# Sheet1.net
KiCad netlist of a schematic drawn in Altium Designer
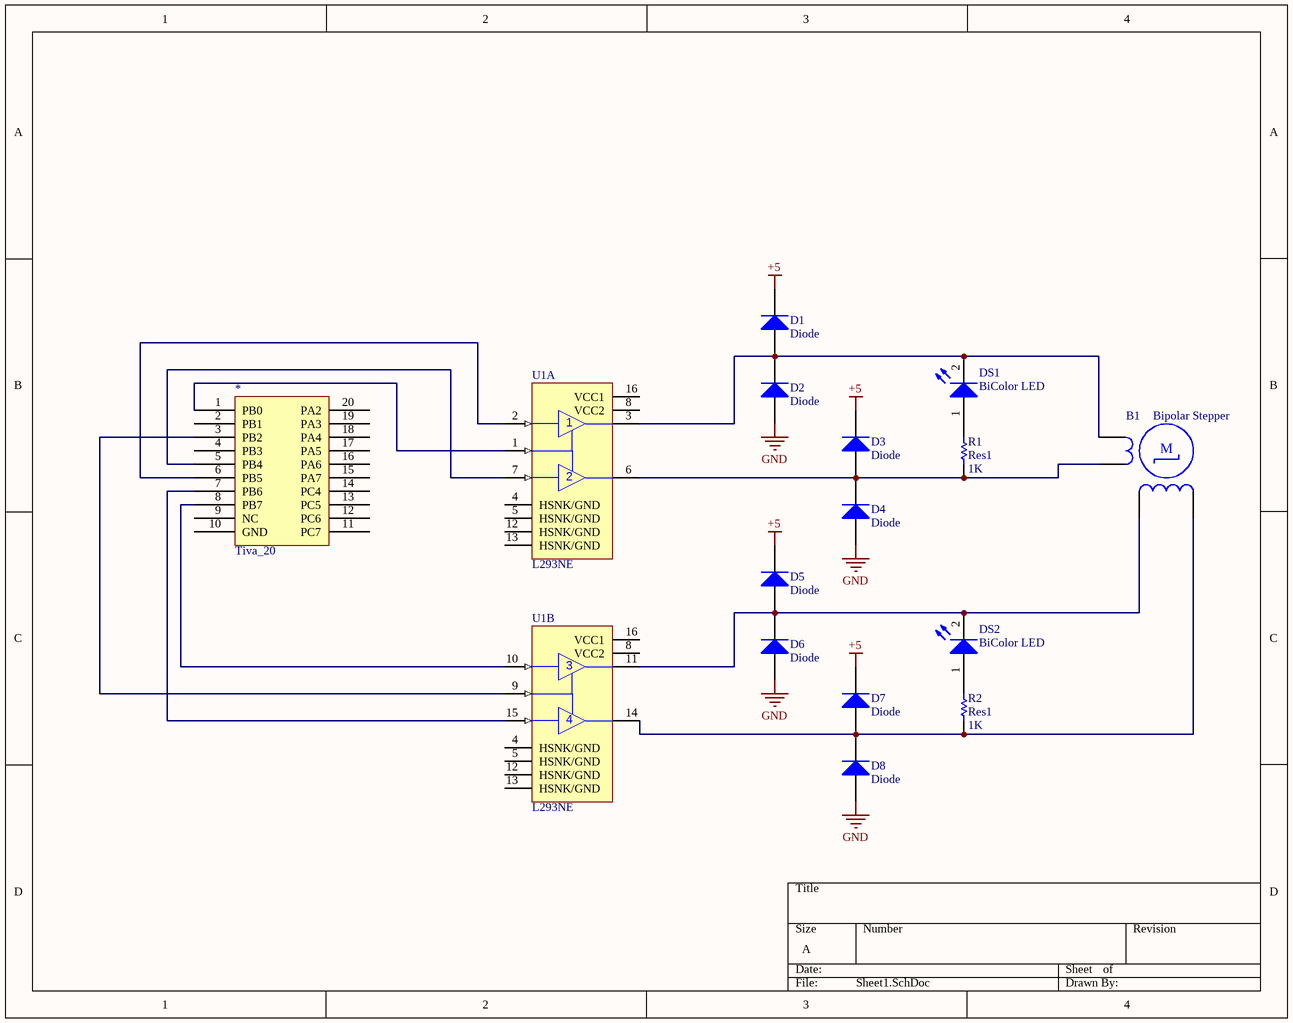
[diagram p0: Sheet1.SchDoc]

(export (version "E")
  (design (tool "Eeschema 10.0.6"))
  (components
    (comp (ref "*")
      (value "Tiva_20")
      (description "Tiva Protection 20 Pin Connector")
      (libsource (lib "ME218_BaseLib") (part "Tiva_20"))
    )
    (comp (ref "B1")
      (value "Bipolar Stepper")
      (footprint "DIP-6")
      (description "Motor Stepper")
      (fields (field (name "MANUFACTURER") "Generic Components"))
      (libsource (lib "ME218_BaseLib") (part "Motor Step 4Wire"))
    )
    (comp (ref "D1")
      (value "Diode")
      (footprint "DSO-C2/X3.3")
      (description "Default Diode")
      (fields
        (field (name "MANUFACTURER") "Generic Components")
        (field (name "PUBLISHER") "Altium Hobart Technology Centre")
      )
      (libsource (lib "ME218_BaseLib") (part "Diode"))
    )
    (comp (ref "D2")
      (value "Diode")
      (footprint "DSO-C2/X3.3")
      (description "Default Diode")
      (fields
        (field (name "MANUFACTURER") "Generic Components")
        (field (name "PUBLISHER") "Altium Hobart Technology Centre")
      )
      (libsource (lib "ME218_BaseLib") (part "Diode"))
    )
    (comp (ref "D3")
      (value "Diode")
      (footprint "DSO-C2/X3.3")
      (description "Default Diode")
      (fields
        (field (name "MANUFACTURER") "Generic Components")
        (field (name "PUBLISHER") "Altium Hobart Technology Centre")
      )
      (libsource (lib "ME218_BaseLib") (part "Diode"))
    )
    (comp (ref "D4")
      (value "Diode")
      (footprint "DSO-C2/X3.3")
      (description "Default Diode")
      (fields
        (field (name "MANUFACTURER") "Generic Components")
        (field (name "PUBLISHER") "Altium Hobart Technology Centre")
      )
      (libsource (lib "ME218_BaseLib") (part "Diode"))
    )
    (comp (ref "D5")
      (value "Diode")
      (footprint "DSO-C2/X3.3")
      (description "Default Diode")
      (fields
        (field (name "MANUFACTURER") "Generic Components")
        (field (name "PUBLISHER") "Altium Hobart Technology Centre")
      )
      (libsource (lib "ME218_BaseLib") (part "Diode"))
    )
    (comp (ref "D6")
      (value "Diode")
      (footprint "DSO-C2/X3.3")
      (description "Default Diode")
      (fields
        (field (name "MANUFACTURER") "Generic Components")
        (field (name "PUBLISHER") "Altium Hobart Technology Centre")
      )
      (libsource (lib "ME218_BaseLib") (part "Diode"))
    )
    (comp (ref "D7")
      (value "Diode")
      (footprint "DSO-C2/X3.3")
      (description "Default Diode")
      (fields
        (field (name "MANUFACTURER") "Generic Components")
        (field (name "PUBLISHER") "Altium Hobart Technology Centre")
      )
      (libsource (lib "ME218_BaseLib") (part "Diode"))
    )
    (comp (ref "D8")
      (value "Diode")
      (footprint "DSO-C2/X3.3")
      (description "Default Diode")
      (fields
        (field (name "MANUFACTURER") "Generic Components")
        (field (name "PUBLISHER") "Altium Hobart Technology Centre")
      )
      (libsource (lib "ME218_BaseLib") (part "Diode"))
    )
    (comp (ref "DS1")
      (value "BiColor LED")
      (footprint "LED-0")
      (description "Typical INFRARED GaAs LED")
      (fields
        (field (name "MANUFACTURER") "Generic Components")
        (field (name "PUBLISHER") "Altium Hobart Technology Centre")
      )
      (libsource (lib "ME218_BaseLib") (part "LED0"))
    )
    (comp (ref "DS2")
      (value "BiColor LED")
      (footprint "LED-0")
      (description "Typical INFRARED GaAs LED")
      (fields
        (field (name "MANUFACTURER") "Generic Components")
        (field (name "PUBLISHER") "Altium Hobart Technology Centre")
      )
      (libsource (lib "ME218_BaseLib") (part "LED0"))
    )
    (comp (ref "R1")
      (value "Res1")
      (footprint "AXIAL-0.3")
      (description "Resistor")
      (fields
        (field (name "MANUFACTURER") "Generic Components")
        (field (name "ALTIUM_VALUE") "1K")
        (field (name "PUBLISHER") "Altium Hobart Technology Centre")
      )
      (libsource (lib "ME218_BaseLib") (part "Res1"))
    )
    (comp (ref "R2")
      (value "Res1")
      (footprint "AXIAL-0.3")
      (description "Resistor")
      (fields
        (field (name "MANUFACTURER") "Generic Components")
        (field (name "ALTIUM_VALUE") "1K")
        (field (name "PUBLISHER") "Altium Hobart Technology Centre")
      )
      (libsource (lib "ME218_BaseLib") (part "Res1"))
    )
    (comp (ref "U1")
      (value "L293NE")
      (footprint "DIP-16/X1.5")
      (description "Quadruple Half-H Driver")
      (fields
        (field (name "MANUFACTURER") "Texas Instruments")
        (field (name "PUBLISHER") "Altium Hobart Technology Centre")
      )
      (libsource (lib "ME218_BaseLib") (part "L293NE"))
    )
  )
  (nets
    (net (code "1") (name "+5") (class "Default")
      (node (ref "D1") (pin "2") (pinfunction "K_2") (pintype "passive"))
      (node (ref "D3") (pin "2") (pinfunction "K_2") (pintype "passive"))
      (node (ref "D5") (pin "2") (pinfunction "K_2") (pintype "passive"))
      (node (ref "D7") (pin "2") (pinfunction "K_2") (pintype "passive"))
    )
    (net (code "2") (name "GND") (class "Default")
      (node (ref "D2") (pin "1") (pinfunction "A_1") (pintype "passive"))
      (node (ref "D4") (pin "1") (pinfunction "A_1") (pintype "passive"))
      (node (ref "D6") (pin "1") (pinfunction "A_1") (pintype "passive"))
      (node (ref "D8") (pin "1") (pinfunction "A_1") (pintype "passive"))
    )
    (net (code "3") (name "Net-(*-PB0)") (class "Default")
      (node (ref "*") (pin "1") (pinfunction "PB0_1") (pintype "passive"))
      (node (ref "U1") (pin "1") (pinfunction "1,2EN_1") (pintype "input"))
    )
    (net (code "4") (name "Net-(*-PB2)") (class "Default")
      (node (ref "*") (pin "3") (pinfunction "PB2_3") (pintype "passive"))
      (node (ref "U1") (pin "9") (pinfunction "3,4EN_9") (pintype "input"))
    )
    (net (code "5") (name "Net-(*-PB4)") (class "Default")
      (node (ref "*") (pin "5") (pinfunction "PB4_5") (pintype "passive"))
      (node (ref "U1") (pin "7") (pinfunction "2A_7") (pintype "input"))
    )
    (net (code "6") (name "Net-(*-PB5)") (class "Default")
      (node (ref "*") (pin "6") (pinfunction "PB5_6") (pintype "passive"))
      (node (ref "U1") (pin "2") (pinfunction "1A_2") (pintype "input"))
    )
    (net (code "7") (name "Net-(*-PB6)") (class "Default")
      (node (ref "*") (pin "7") (pinfunction "PB6_7") (pintype "passive"))
      (node (ref "U1") (pin "15") (pinfunction "4A_15") (pintype "input"))
    )
    (net (code "8") (name "Net-(*-PB7)") (class "Default")
      (node (ref "*") (pin "8") (pinfunction "PB7_8") (pintype "passive"))
      (node (ref "U1") (pin "10") (pinfunction "3A_10") (pintype "input"))
    )
    (net (code "9") (name "Net-(D1-A)") (class "Default")
      (node (ref "B1") (pin "1") (pinfunction "1_1") (pintype "passive"))
      (node (ref "D1") (pin "1") (pinfunction "A_1") (pintype "passive"))
      (node (ref "D2") (pin "2") (pinfunction "K_2") (pintype "passive"))
      (node (ref "DS1") (pin "2") (pinfunction "K_2") (pintype "passive"))
      (node (ref "U1") (pin "3") (pinfunction "1Y_3") (pintype "tri_state"))
    )
    (net (code "10") (name "Net-(D3-A)") (class "Default")
      (node (ref "B1") (pin "3") (pinfunction "3_3") (pintype "passive"))
      (node (ref "D3") (pin "1") (pinfunction "A_1") (pintype "passive"))
      (node (ref "D4") (pin "2") (pinfunction "K_2") (pintype "passive"))
      (node (ref "R1") (pin "1") (pinfunction "1_1") (pintype "passive"))
      (node (ref "U1") (pin "6") (pinfunction "2Y_6") (pintype "tri_state"))
    )
    (net (code "11") (name "Net-(D5-A)") (class "Default")
      (node (ref "B1") (pin "4") (pinfunction "4_4") (pintype "passive"))
      (node (ref "D5") (pin "1") (pinfunction "A_1") (pintype "passive"))
      (node (ref "D6") (pin "2") (pinfunction "K_2") (pintype "passive"))
      (node (ref "DS2") (pin "2") (pinfunction "K_2") (pintype "passive"))
      (node (ref "U1") (pin "11") (pinfunction "3Y_11") (pintype "tri_state"))
    )
    (net (code "12") (name "Net-(D7-A)") (class "Default")
      (node (ref "B1") (pin "6") (pinfunction "6_6") (pintype "passive"))
      (node (ref "D7") (pin "1") (pinfunction "A_1") (pintype "passive"))
      (node (ref "D8") (pin "2") (pinfunction "K_2") (pintype "passive"))
      (node (ref "R2") (pin "1") (pinfunction "1_1") (pintype "passive"))
      (node (ref "U1") (pin "14") (pinfunction "4Y_14") (pintype "tri_state"))
    )
    (net (code "13") (name "Net-(DS1-A)") (class "Default")
      (node (ref "DS1") (pin "1") (pinfunction "A_1") (pintype "passive"))
      (node (ref "R1") (pin "2") (pinfunction "2_2") (pintype "passive"))
    )
    (net (code "14") (name "Net-(DS2-A)") (class "Default")
      (node (ref "DS2") (pin "1") (pinfunction "A_1") (pintype "passive"))
      (node (ref "R2") (pin "2") (pinfunction "2_2") (pintype "passive"))
    )
    (net (code "15") (name "unconnected-(*-GND-Pad10)") (class "Default")
      (node (ref "*") (pin "10") (pinfunction "GND_10") (pintype "passive"))
    )
    (net (code "16") (name "unconnected-(*-NC-Pad9)") (class "Default")
      (node (ref "*") (pin "9") (pinfunction "NC_9") (pintype "passive"))
    )
    (net (code "17") (name "unconnected-(*-PA2-Pad20)") (class "Default")
      (node (ref "*") (pin "20") (pinfunction "PA2_20") (pintype "passive"))
    )
    (net (code "18") (name "unconnected-(*-PA3-Pad19)") (class "Default")
      (node (ref "*") (pin "19") (pinfunction "PA3_19") (pintype "passive"))
    )
    (net (code "19") (name "unconnected-(*-PA4-Pad18)") (class "Default")
      (node (ref "*") (pin "18") (pinfunction "PA4_18") (pintype "passive"))
    )
    (net (code "20") (name "unconnected-(*-PA5-Pad17)") (class "Default")
      (node (ref "*") (pin "17") (pinfunction "PA5_17") (pintype "passive"))
    )
    (net (code "21") (name "unconnected-(*-PA6-Pad16)") (class "Default")
      (node (ref "*") (pin "16") (pinfunction "PA6_16") (pintype "passive"))
    )
    (net (code "22") (name "unconnected-(*-PA7-Pad15)") (class "Default")
      (node (ref "*") (pin "15") (pinfunction "PA7_15") (pintype "passive"))
    )
    (net (code "23") (name "unconnected-(*-PB1-Pad2)") (class "Default")
      (node (ref "*") (pin "2") (pinfunction "PB1_2") (pintype "passive"))
    )
    (net (code "24") (name "unconnected-(*-PB3-Pad4)") (class "Default")
      (node (ref "*") (pin "4") (pinfunction "PB3_4") (pintype "passive"))
    )
    (net (code "25") (name "unconnected-(*-PC4-Pad14)") (class "Default")
      (node (ref "*") (pin "14") (pinfunction "PC4_14") (pintype "passive"))
    )
    (net (code "26") (name "unconnected-(*-PC5-Pad13)") (class "Default")
      (node (ref "*") (pin "13") (pinfunction "PC5_13") (pintype "passive"))
    )
    (net (code "27") (name "unconnected-(*-PC6-Pad12)") (class "Default")
      (node (ref "*") (pin "12") (pinfunction "PC6_12") (pintype "passive"))
    )
    (net (code "28") (name "unconnected-(*-PC7-Pad11)") (class "Default")
      (node (ref "*") (pin "11") (pinfunction "PC7_11") (pintype "passive"))
    )
    (net (code "29") (name "unconnected-(U1A-HSNK{slash}GND-Pad4)") (class "Default")
      (node (ref "U1") (pin "4") (pinfunction "HSNK/GND_4") (pintype "power_in"))
    )
    (net (code "30") (name "unconnected-(U1A-HSNK{slash}GND-Pad5)") (class "Default")
      (node (ref "U1") (pin "5") (pinfunction "HSNK/GND_5") (pintype "power_in"))
    )
    (net (code "31") (name "unconnected-(U1A-HSNK{slash}GND-Pad12)") (class "Default")
      (node (ref "U1") (pin "12") (pinfunction "HSNK/GND_12") (pintype "power_in"))
    )
    (net (code "32") (name "unconnected-(U1A-HSNK{slash}GND-Pad13)") (class "Default")
      (node (ref "U1") (pin "13") (pinfunction "HSNK/GND_13") (pintype "power_in"))
    )
    (net (code "33") (name "unconnected-(U1A-VCC1-Pad16)") (class "Default")
      (node (ref "U1") (pin "16") (pinfunction "VCC1_16") (pintype "power_in"))
    )
    (net (code "34") (name "unconnected-(U1A-VCC2-Pad8)") (class "Default")
      (node (ref "U1") (pin "8") (pinfunction "VCC2_8") (pintype "power_in"))
    )
    (net (code "35") (name "unconnected-(U1B-HSNK{slash}GND-Pad4)") (class "Default")
      (node (ref "U1") (pin "4") (pinfunction "HSNK/GND_4") (pintype "power_in"))
    )
    (net (code "36") (name "unconnected-(U1B-HSNK{slash}GND-Pad5)") (class "Default")
      (node (ref "U1") (pin "5") (pinfunction "HSNK/GND_5") (pintype "power_in"))
    )
    (net (code "37") (name "unconnected-(U1B-HSNK{slash}GND-Pad12)") (class "Default")
      (node (ref "U1") (pin "12") (pinfunction "HSNK/GND_12") (pintype "power_in"))
    )
    (net (code "38") (name "unconnected-(U1B-HSNK{slash}GND-Pad13)") (class "Default")
      (node (ref "U1") (pin "13") (pinfunction "HSNK/GND_13") (pintype "power_in"))
    )
    (net (code "39") (name "unconnected-(U1B-VCC1-Pad16)") (class "Default")
      (node (ref "U1") (pin "16") (pinfunction "VCC1_16") (pintype "power_in"))
    )
    (net (code "40") (name "unconnected-(U1B-VCC2-Pad8)") (class "Default")
      (node (ref "U1") (pin "8") (pinfunction "VCC2_8") (pintype "power_in"))
    )
  )
)
